# M8-Thermocouple.net
KiCad netlist of a schematic drawn in EAGLE
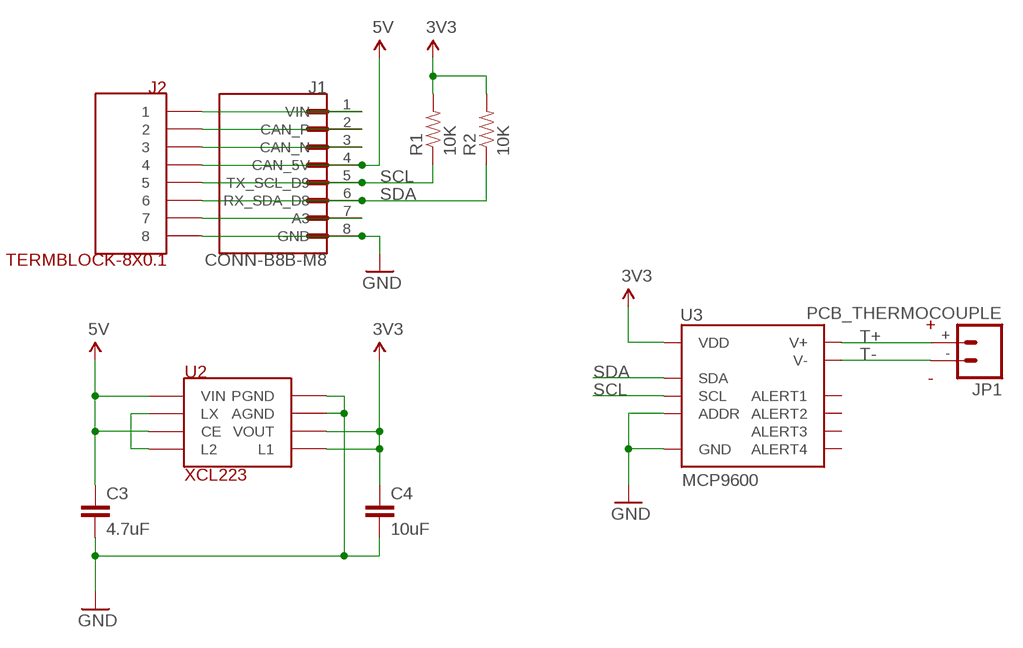
[diagram p0: schematic, sheet 1]

(export (version "E")
  (design (tool "Eeschema 10.0.6"))
  (components
    (comp (ref "C3")
      (value "4.7uF")
      (footprint "eagle-import:0603-CAP")
      (libsource (lib "eagle-import") (part "CAP-4.7UF-0603"))
    )
    (comp (ref "C4")
      (value "10uF")
      (footprint "eagle-import:0603-CAP")
      (libsource (lib "eagle-import") (part "CAP-10UF-0603"))
    )
    (comp (ref "J1")
      (value "CONN-B8B-M8")
      (footprint "eagle-import:JST_B8B-PH-SM4-TB(LF)(SN)")
      (libsource (lib "eagle-import") (part "CONN-B8B-M8"))
    )
    (comp (ref "J2")
      (value "TERMBLOCK-8X0.1")
      (footprint "eagle-import:TERMBLOCK-8X0.1")
      (libsource (lib "eagle-import") (part "TERMBLOCK-8X0.1"))
    )
    (comp (ref "JP1")
      (value "PCB_THERMOCOUPLE")
      (footprint "eagle-import:PCC-SMP")
      (libsource (lib "eagle-import") (part "PCB_THERMOCOUPLE"))
    )
    (comp (ref "R1")
      (value "10K")
      (footprint "eagle-import:0603-RES")
      (libsource (lib "eagle-import") (part "RES-10K-06030603"))
    )
    (comp (ref "R2")
      (value "10K")
      (footprint "eagle-import:0603-RES")
      (libsource (lib "eagle-import") (part "RES-10K-06030603"))
    )
    (comp (ref "U2")
      (value "XCL223")
      (footprint "eagle-import:REG-XCL223-LESS-CREAM")
      (libsource (lib "eagle-import") (part "REG-XCL223"))
    )
    (comp (ref "U3")
      (value "MCP9600")
      (footprint "eagle-import:MQFN-20")
      (libsource (lib "eagle-import") (part "MCP9600-SMD"))
    )
  )
  (nets
    (net (code "1") (name "/SCL") (class "Default")
      (node (ref "J1") (pin "5") (pinfunction "TX_SCL_D9_5") (pintype "passive"))
      (node (ref "J2") (pin "P$5") (pinfunction "5_P$5") (pintype "passive"))
      (node (ref "R1") (pin "1") (pinfunction "1_1") (pintype "passive"))
      (node (ref "U3") (pin "19") (pinfunction "SCL_19") (pintype "bidirectional"))
    )
    (net (code "2") (name "/SDA") (class "Default")
      (node (ref "J1") (pin "6") (pinfunction "RX_SDA_D8_6") (pintype "passive"))
      (node (ref "J2") (pin "P$6") (pinfunction "6_P$6") (pintype "passive"))
      (node (ref "R2") (pin "1") (pinfunction "1_1") (pintype "passive"))
      (node (ref "U3") (pin "20") (pinfunction "SDA_20") (pintype "bidirectional"))
    )
    (net (code "3") (name "/T+") (class "Default")
      (node (ref "JP1") (pin "+") (pinfunction "+_+") (pintype "passive"))
      (node (ref "U3") (pin "2") (pinfunction "V+_2") (pintype "bidirectional"))
    )
    (net (code "4") (name "/T-") (class "Default")
      (node (ref "JP1") (pin "-") (pinfunction "-_-") (pintype "passive"))
      (node (ref "U3") (pin "4") (pinfunction "V-_4") (pintype "bidirectional"))
    )
    (net (code "5") (name "3V3") (class "Default")
      (node (ref "C4") (pin "1") (pinfunction "1_1") (pintype "passive"))
      (node (ref "R1") (pin "2") (pinfunction "2_2") (pintype "passive"))
      (node (ref "R2") (pin "2") (pinfunction "2_2") (pintype "passive"))
      (node (ref "U2") (pin "3") (pinfunction "VOUT_3") (pintype "passive"))
      (node (ref "U2") (pin "7") (pinfunction "L1_7") (pintype "passive"))
      (node (ref "U3") (pin "8") (pinfunction "VDD_8") (pintype "bidirectional"))
    )
    (net (code "6") (name "5V") (class "Default")
      (node (ref "C3") (pin "1") (pinfunction "1_1") (pintype "passive"))
      (node (ref "J1") (pin "4") (pinfunction "CAN_5V_4") (pintype "passive"))
      (node (ref "J2") (pin "P$4") (pinfunction "4_P$4") (pintype "passive"))
      (node (ref "U2") (pin "4") (pinfunction "CE_4") (pintype "input"))
      (node (ref "U2") (pin "6") (pinfunction "VIN_6") (pintype "power_in"))
    )
    (net (code "7") (name "GND") (class "Default")
      (node (ref "C3") (pin "2") (pinfunction "2_2") (pintype "passive"))
      (node (ref "C4") (pin "2") (pinfunction "2_2") (pintype "passive"))
      (node (ref "J1") (pin "8") (pinfunction "GND_8") (pintype "passive"))
      (node (ref "J2") (pin "P$8") (pinfunction "8_P$8") (pintype "passive"))
      (node (ref "U2") (pin "1") (pinfunction "PGND_1") (pintype "passive"))
      (node (ref "U2") (pin "2") (pinfunction "AGND_2") (pintype "passive"))
      (node (ref "U3") (pin "1") (pinfunction "GND_1") (pintype "bidirectional"))
      (node (ref "U3") (pin "10") (pinfunction "GND_10") (pintype "bidirectional"))
      (node (ref "U3") (pin "13") (pinfunction "GND_13") (pintype "bidirectional"))
      (node (ref "U3") (pin "16") (pinfunction "ADDR_16") (pintype "bidirectional"))
      (node (ref "U3") (pin "17") (pinfunction "GND_17") (pintype "bidirectional"))
      (node (ref "U3") (pin "18") (pinfunction "GND_18") (pintype "bidirectional"))
      (node (ref "U3") (pin "21") (pinfunction "GND_21") (pintype "bidirectional"))
      (node (ref "U3") (pin "3") (pinfunction "GND_3") (pintype "bidirectional"))
      (node (ref "U3") (pin "5") (pinfunction "GND_5") (pintype "bidirectional"))
      (node (ref "U3") (pin "6") (pinfunction "GND_6") (pintype "bidirectional"))
      (node (ref "U3") (pin "7") (pinfunction "GND_7") (pintype "bidirectional"))
      (node (ref "U3") (pin "9") (pinfunction "GND_9") (pintype "bidirectional"))
    )
    (net (code "8") (name "Net-(J1-A3)") (class "Default")
      (node (ref "J1") (pin "7") (pinfunction "A3_7") (pintype "passive"))
      (node (ref "J2") (pin "P$7") (pinfunction "7_P$7") (pintype "passive"))
    )
    (net (code "9") (name "Net-(J1-CAN_N)") (class "Default")
      (node (ref "J1") (pin "3") (pinfunction "CAN_N_3") (pintype "passive"))
      (node (ref "J2") (pin "P$3") (pinfunction "3_P$3") (pintype "passive"))
    )
    (net (code "10") (name "Net-(J1-CAN_P)") (class "Default")
      (node (ref "J1") (pin "2") (pinfunction "CAN_P_2") (pintype "passive"))
      (node (ref "J2") (pin "P$2") (pinfunction "2_P$2") (pintype "passive"))
    )
    (net (code "11") (name "Net-(J1-VIN)") (class "Default")
      (node (ref "J1") (pin "1") (pinfunction "VIN_1") (pintype "passive"))
      (node (ref "J2") (pin "P$1") (pinfunction "1_P$1") (pintype "passive"))
    )
    (net (code "12") (name "Net-(U2-L2)") (class "Default")
      (node (ref "U2") (pin "5") (pinfunction "LX_5") (pintype "passive"))
      (node (ref "U2") (pin "8") (pinfunction "L2_8") (pintype "passive"))
    )
    (net (code "13") (name "unconnected-(U3-ALERT1-Pad11)") (class "Default")
      (node (ref "U3") (pin "11") (pinfunction "ALERT1_11") (pintype "bidirectional"))
    )
    (net (code "14") (name "unconnected-(U3-ALERT2-Pad12)") (class "Default")
      (node (ref "U3") (pin "12") (pinfunction "ALERT2_12") (pintype "bidirectional"))
    )
    (net (code "15") (name "unconnected-(U3-ALERT3-Pad14)") (class "Default")
      (node (ref "U3") (pin "14") (pinfunction "ALERT3_14") (pintype "bidirectional"))
    )
    (net (code "16") (name "unconnected-(U3-ALERT4-Pad15)") (class "Default")
      (node (ref "U3") (pin "15") (pinfunction "ALERT4_15") (pintype "bidirectional"))
    )
  )
)
